# 1_Controller.net
KiCad netlist of a schematic drawn in Altium Designer
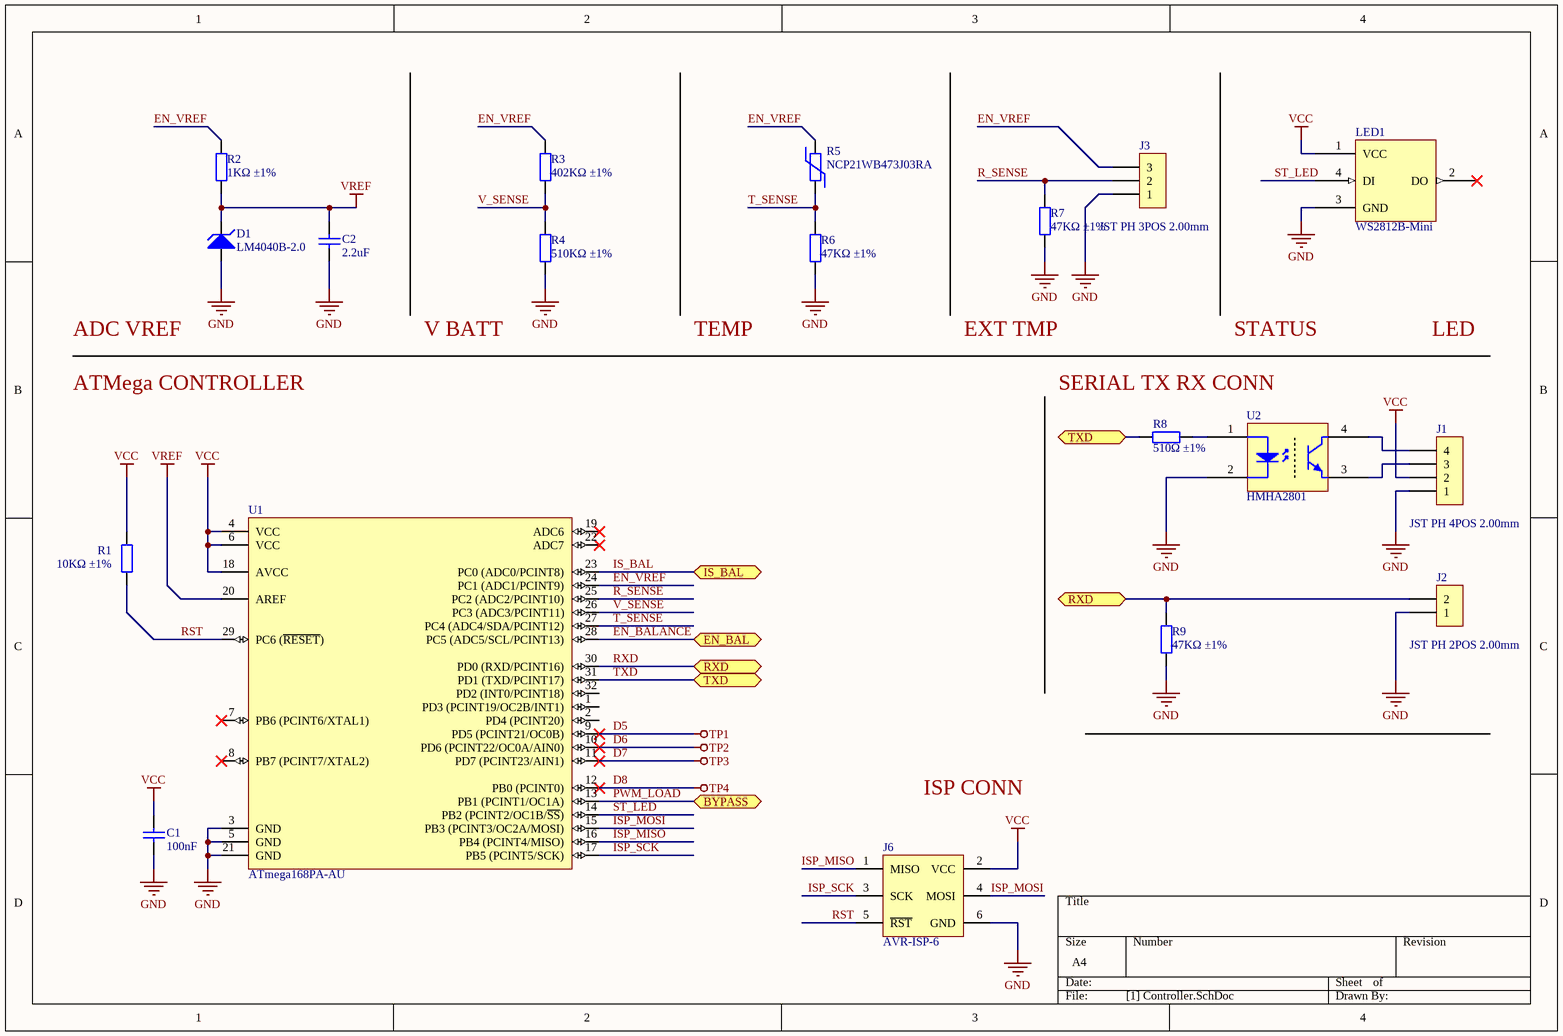
[diagram p0: [1] Controller.SchDoc]

(export (version "E")
  (design (tool "Eeschema 10.0.6"))
  (components
    (comp (ref "C1")
      (value "100nF")
      (footprint "0805_C")
      (description "Chip capacitors")
      (fields (field (name "MANUFACTURER") "YAGEO") (field (name "PARTNUMBER") "CC0805KRX7R9BB104"))
      (libsource (lib "Miscellaneous Devices LC") (part "0805 100nF(104) 10% 50V"))
    )
    (comp (ref "C2")
      (value "2.2uF")
      (footprint "0805_C")
      (description "Chip capacitors")
      (fields
        (field (name "MANUFACTURER") "Guangdong Fenghua Advanced Tech")
        (field (name "PARTNUMBER") "0805F225M500NT")
      )
      (libsource (lib "Miscellaneous Devices LC") (part "0805 2.2uF (225) 20% 50V"))
    )
    (comp (ref "D1")
      (value "LM4040B-2.0")
      (footprint "SOT-23(SOT-23-3)")
      (description "Precision Shunt Voltage Reference")
      (libsource (lib "BMS_SchLib") (part "LM4040B-2.0"))
    )
    (comp (ref "J1")
      (value "JST PH 4POS 2.00mm")
      (footprint "JST_PH_S4B")
      (description "JST-PH Conn")
      (fields
        (field (name "MANUFACTURER") "JST Sales America")
        (field (name "PARTNUMBER") "S4B-PH-K-S(LF)(SN)")
      )
      (libsource (lib "BMS_SchLib") (part "JST_PH_4POS"))
    )
    (comp (ref "J2")
      (value "JST PH 2POS 2.00mm")
      (footprint "JST_PH_S2B")
      (description "JST-PH Conn")
      (fields
        (field (name "MANUFACTURER") "JST Sales America")
        (field (name "PARTNUMBER") "S2B-PH-K-S(LF)(SN)")
      )
      (libsource (lib "BMS_SchLib") (part "JST_PH_2POS"))
    )
    (comp (ref "J3")
      (value "JST PH 3POS 2.00mm")
      (footprint "JST_PH_S3B")
      (description "JST-PH Conn")
      (fields
        (field (name "MANUFACTURER") "JST Sales America")
        (field (name "PARTNUMBER") "S3B-PH-K-S(LF)(SN)")
      )
      (libsource (lib "BMS_SchLib") (part "JST_PH_3POS"))
    )
    (comp (ref "J6")
      (value "AVR-ISP-6")
      (footprint "PINHEADER_6POS_2ROW_2.54")
      (fields (field (name "MANUFACTURER") "Boom Precision Elec") (field (name "PARTNUMBER") "C65114"))
      (libsource (lib "BMS_SchLib") (part "AVR_ISP"))
    )
    (comp (ref "LED1")
      (value "WS2812B-Mini")
      (footprint "LED3535_4P")
      (description "RGB Addressable LED")
      (fields (field (name "MANUFACTURER") "Worldsemi"))
      (libsource (lib "BMS_SchLib") (part "WS2812B-Mini"))
    )
    (comp (ref "R1")
      (value "10KΩ ±1%")
      (footprint "0805_R")
      (description "Chip resistor")
      (fields (field (name "MANUFACTURER") "Uniroyal Elec") (field (name "PARTNUMBER") "0805W8F1002T5E"))
      (libsource (lib "RES") (part "0805 10K (1002) 1%"))
    )
    (comp (ref "R2")
      (value "1KΩ ±1%")
      (footprint "0805_R")
      (description "Chip resistor")
      (fields (field (name "MANUFACTURER") "Uniroyal Elec") (field (name "PARTNUMBER") "0805W8F1001T5E"))
      (libsource (lib "RES") (part "0805 1K (1001) 1%"))
    )
    (comp (ref "R3")
      (value "402KΩ ±1%")
      (footprint "0805_R")
      (description "Chip resistor")
      (fields (field (name "MANUFACTURER") "Uniroyal Elec") (field (name "PARTNUMBER") "0805W8F4023T5E"))
      (libsource (lib "BMS_SchLib") (part "0805 402K (4023) 1%"))
    )
    (comp (ref "R4")
      (value "510KΩ ±1%")
      (footprint "0805_R")
      (description "Chip resistor")
      (fields (field (name "MANUFACTURER") "Uniroyal Elec") (field (name "PARTNUMBER") "0805W8F4023T5E"))
      (libsource (lib "BMS_SchLib") (part "0805 510K (5103) 1%"))
    )
    (comp (ref "R5")
      (value "NCP21WB473J03RA")
      (footprint "0805_R")
      (description "NTC Resistor 47K 5%")
      (fields (field (name "MANUFACTURER") "Murata Electronics") (field (name "TOLERANCE") "5%"))
      (libsource (lib "BMS_SchLib") (part "0805 NTC 47K 5%"))
    )
    (comp (ref "R6")
      (value "47KΩ ±1%")
      (footprint "0805_R")
      (description "Chip resistor")
      (fields (field (name "MANUFACTURER") "Uniroyal Elec") (field (name "PARTNUMBER") "0805W8F4702T5E"))
      (libsource (lib "RES") (part "0805 47K (4702) 1%"))
    )
    (comp (ref "R7")
      (value "47KΩ ±1%")
      (footprint "0805_R")
      (description "Chip resistor")
      (fields (field (name "MANUFACTURER") "Uniroyal Elec") (field (name "PARTNUMBER") "0805W8F4702T5E"))
      (libsource (lib "RES") (part "0805 47K (4702) 1%"))
    )
    (comp (ref "R8")
      (value "510Ω ±1%")
      (footprint "0805_R")
      (description "Chip resistor")
      (fields (field (name "MANUFACTURER") "Uniroyal Elec") (field (name "PARTNUMBER") "0805W8F5100T5E"))
      (libsource (lib "RES") (part "0805 510R (5100) 1%"))
    )
    (comp (ref "R9")
      (value "47KΩ ±1%")
      (footprint "0805_R")
      (description "Chip resistor")
      (fields (field (name "MANUFACTURER") "Uniroyal Elec") (field (name "PARTNUMBER") "0805W8F4702T5E"))
      (libsource (lib "RES") (part "0805 47K (4702) 1%"))
    )
    (comp (ref "U1")
      (value "ATmega168PA-AU")
      (footprint "TQFP-32_7x7x08P")
      (description "ATmega AVR")
      (fields (field (name "MANUFACTURER") "Microchip Tech") (field (name "PARTNUMBER") "ATMEGA168PA-AU"))
      (libsource (lib "BMS_SchLib") (part "ATMEGA168"))
    )
    (comp (ref "U2")
      (value "HMHA2801")
      (footprint "HMHA2801")
      (description "Optocoupler")
      (fields (field (name "MANUFACTURER") "ON Semicon") (field (name "PARTNUMBER") "HMHA2801AR2"))
      (libsource (lib "BMS_SchLib") (part "HMHA2801"))
    )
  )
  (nets
    (net (code "1") (name "/EN_BALANCE") (class "Default")
      (node (ref "U1") (pin "28") (pinfunction "PC5_(ADC5/SCL/PCINT13)_28") (pintype "bidirectional"))
    )
    (net (code "2") (name "/EN_VREF") (class "Default")
      (node (ref "J3") (pin "3") (pinfunction "3_3") (pintype "passive"))
      (node (ref "R2") (pin "2") (pinfunction "2_2") (pintype "passive"))
      (node (ref "R3") (pin "2") (pinfunction "2_2") (pintype "passive"))
      (node (ref "R5") (pin "2") (pinfunction "2_2") (pintype "passive"))
      (node (ref "U1") (pin "24") (pinfunction "PC1_(ADC1/PCINT9)_24") (pintype "bidirectional"))
    )
    (net (code "3") (name "/ISP_MISO") (class "Default")
      (node (ref "J6") (pin "1") (pinfunction "MISO_1") (pintype "passive"))
      (node (ref "U1") (pin "16") (pinfunction "PB4_(PCINT4/MISO)_16") (pintype "bidirectional"))
    )
    (net (code "4") (name "/ISP_MOSI") (class "Default")
      (node (ref "J6") (pin "4") (pinfunction "MOSI_4") (pintype "passive"))
      (node (ref "U1") (pin "15") (pinfunction "PB3_(PCINT3/OC2A/MOSI)_15") (pintype "bidirectional"))
    )
    (net (code "5") (name "/ISP_SCK") (class "Default")
      (node (ref "J6") (pin "3") (pinfunction "SCK_3") (pintype "passive"))
      (node (ref "U1") (pin "17") (pinfunction "PB5_(PCINT5/SCK)_17") (pintype "bidirectional"))
    )
    (net (code "6") (name "/IS_BAL") (class "Default")
      (node (ref "U1") (pin "23") (pinfunction "PC0_(ADC0/PCINT8)_23") (pintype "bidirectional"))
    )
    (net (code "7") (name "/PWM_LOAD") (class "Default")
      (node (ref "U1") (pin "13") (pinfunction "PB1_(PCINT1/OC1A)_13") (pintype "bidirectional"))
    )
    (net (code "8") (name "/RST") (class "Default")
      (node (ref "J6") (pin "5") (pinfunction "~{RST}_5") (pintype "passive"))
      (node (ref "R1") (pin "2") (pinfunction "2_2") (pintype "passive"))
      (node (ref "U1") (pin "29") (pinfunction "PC6_(~{RESET})_29") (pintype "bidirectional"))
    )
    (net (code "9") (name "/RXD") (class "Default")
      (node (ref "J2") (pin "2") (pinfunction "2_2") (pintype "passive"))
      (node (ref "R9") (pin "2") (pinfunction "2_2") (pintype "passive"))
      (node (ref "U1") (pin "30") (pinfunction "PD0_(RXD/PCINT16)_30") (pintype "bidirectional"))
    )
    (net (code "10") (name "/R_SENSE") (class "Default")
      (node (ref "J3") (pin "2") (pinfunction "2_2") (pintype "passive"))
      (node (ref "R7") (pin "2") (pinfunction "2_2") (pintype "passive"))
      (node (ref "U1") (pin "25") (pinfunction "PC2_(ADC2/PCINT10)_25") (pintype "bidirectional"))
    )
    (net (code "11") (name "/ST_LED") (class "Default")
      (node (ref "LED1") (pin "4") (pinfunction "DI_4") (pintype "input"))
      (node (ref "U1") (pin "14") (pinfunction "PB2_(PCINT2/OC1B/~{SS})_14") (pintype "bidirectional"))
    )
    (net (code "12") (name "/TXD") (class "Default")
      (node (ref "R8") (pin "1") (pinfunction "1_1") (pintype "passive"))
      (node (ref "U1") (pin "31") (pinfunction "PD1_(TXD/PCINT17)_31") (pintype "bidirectional"))
    )
    (net (code "13") (name "/T_SENSE") (class "Default")
      (node (ref "R5") (pin "1") (pinfunction "1_1") (pintype "passive"))
      (node (ref "R6") (pin "2") (pinfunction "2_2") (pintype "passive"))
      (node (ref "U1") (pin "27") (pinfunction "PC4_(ADC4/SDA/PCINT12)_27") (pintype "bidirectional"))
    )
    (net (code "14") (name "/V_SENSE") (class "Default")
      (node (ref "R3") (pin "1") (pinfunction "1_1") (pintype "passive"))
      (node (ref "R4") (pin "2") (pinfunction "2_2") (pintype "passive"))
      (node (ref "U1") (pin "26") (pinfunction "PC3_(ADC3/PCINT11)_26") (pintype "bidirectional"))
    )
    (net (code "15") (name "GND") (class "Default")
      (node (ref "C1") (pin "1") (pinfunction "1_1") (pintype "passive"))
      (node (ref "C2") (pin "1") (pinfunction "1_1") (pintype "passive"))
      (node (ref "D1") (pin "2") (pinfunction "A_2") (pintype "passive"))
      (node (ref "J1") (pin "1") (pinfunction "1_1") (pintype "passive"))
      (node (ref "J2") (pin "1") (pinfunction "1_1") (pintype "passive"))
      (node (ref "J3") (pin "1") (pinfunction "1_1") (pintype "passive"))
      (node (ref "J6") (pin "6") (pinfunction "GND_6") (pintype "power_in"))
      (node (ref "LED1") (pin "3") (pinfunction "GND_3") (pintype "power_in"))
      (node (ref "R4") (pin "1") (pinfunction "1_1") (pintype "passive"))
      (node (ref "R6") (pin "1") (pinfunction "1_1") (pintype "passive"))
      (node (ref "R7") (pin "1") (pinfunction "1_1") (pintype "passive"))
      (node (ref "R9") (pin "1") (pinfunction "1_1") (pintype "passive"))
      (node (ref "U1") (pin "21") (pinfunction "GND_21") (pintype "power_in"))
      (node (ref "U1") (pin "3") (pinfunction "GND_3") (pintype "power_in"))
      (node (ref "U1") (pin "5") (pinfunction "GND_5") (pintype "power_in"))
      (node (ref "U2") (pin "2") (pinfunction "A_2") (pintype "passive"))
    )
    (net (code "16") (name "Net-(J1-Pad3)") (class "Default")
      (node (ref "J1") (pin "3") (pinfunction "3_3") (pintype "passive"))
      (node (ref "U2") (pin "3") (pintype "passive"))
    )
    (net (code "17") (name "Net-(J1-Pad4)") (class "Default")
      (node (ref "J1") (pin "4") (pinfunction "4_4") (pintype "passive"))
      (node (ref "U2") (pin "4") (pintype "passive"))
    )
    (net (code "18") (name "Net-(R8-Pad2)") (class "Default")
      (node (ref "R8") (pin "2") (pinfunction "2_2") (pintype "passive"))
      (node (ref "U2") (pin "1") (pintype "passive"))
    )
    (net (code "19") (name "TP1") (class "Default")
      (node (ref "U1") (pin "9") (pinfunction "PD5_(PCINT21/OC0B)_9") (pintype "bidirectional"))
    )
    (net (code "20") (name "TP2") (class "Default")
      (node (ref "U1") (pin "10") (pinfunction "PD6_(PCINT22/OC0A/AIN0)_10") (pintype "bidirectional"))
    )
    (net (code "21") (name "TP3") (class "Default")
      (node (ref "U1") (pin "11") (pinfunction "PD7_(PCINT23/AIN1)_11") (pintype "bidirectional"))
    )
    (net (code "22") (name "TP4") (class "Default")
      (node (ref "U1") (pin "12") (pinfunction "PB0_(PCINT0)_12") (pintype "bidirectional"))
    )
    (net (code "23") (name "VCC") (class "Default")
      (node (ref "C1") (pin "2") (pinfunction "2_2") (pintype "passive"))
      (node (ref "J1") (pin "2") (pinfunction "2_2") (pintype "passive"))
      (node (ref "J6") (pin "2") (pinfunction "VCC_2") (pintype "power_in"))
      (node (ref "LED1") (pin "1") (pinfunction "VCC_1") (pintype "power_in"))
      (node (ref "R1") (pin "1") (pinfunction "1_1") (pintype "passive"))
      (node (ref "U1") (pin "18") (pinfunction "AVCC_18") (pintype "passive"))
      (node (ref "U1") (pin "4") (pinfunction "VCC_4") (pintype "passive"))
      (node (ref "U1") (pin "6") (pinfunction "VCC_6") (pintype "passive"))
    )
    (net (code "24") (name "VREF") (class "Default")
      (node (ref "C2") (pin "2") (pinfunction "2_2") (pintype "passive"))
      (node (ref "D1") (pin "1") (pinfunction "K_1") (pintype "passive"))
      (node (ref "R2") (pin "1") (pinfunction "1_1") (pintype "passive"))
      (node (ref "U1") (pin "20") (pinfunction "AREF_20") (pintype "passive"))
    )
    (net (code "25") (name "unconnected-(LED1-DO-Pad2)") (class "Default")
      (node (ref "LED1") (pin "2") (pinfunction "DO_2") (pintype "output+no_connect"))
    )
    (net (code "26") (name "unconnected-(U1-ADC6-Pad19)") (class "Default")
      (node (ref "U1") (pin "19") (pinfunction "ADC6_19") (pintype "bidirectional+no_connect"))
    )
    (net (code "27") (name "unconnected-(U1-ADC7-Pad22)") (class "Default")
      (node (ref "U1") (pin "22") (pinfunction "ADC7_22") (pintype "bidirectional+no_connect"))
    )
    (net (code "28") (name "unconnected-(U1-PB6_(PCINT6{slash}XTAL1)-Pad7)") (class "Default")
      (node (ref "U1") (pin "7") (pinfunction "PB6_(PCINT6/XTAL1)_7") (pintype "bidirectional+no_connect"))
    )
    (net (code "29") (name "unconnected-(U1-PB7_(PCINT7{slash}XTAL2)-Pad8)") (class "Default")
      (node (ref "U1") (pin "8") (pinfunction "PB7_(PCINT7/XTAL2)_8") (pintype "bidirectional+no_connect"))
    )
    (net (code "30") (name "unconnected-(U1-PD2_(INT0{slash}PCINT18)-Pad32)") (class "Default")
      (node (ref "U1") (pin "32") (pinfunction "PD2_(INT0/PCINT18)_32") (pintype "bidirectional"))
    )
    (net (code "31") (name "unconnected-(U1-PD3_(PCINT19{slash}OC2B{slash}INT1)-Pad1)") (class "Default")
      (node (ref "U1") (pin "1") (pinfunction "PD3_(PCINT19/OC2B/INT1)_1") (pintype "bidirectional"))
    )
    (net (code "32") (name "unconnected-(U1-PD4_(PCINT20)-Pad2)") (class "Default")
      (node (ref "U1") (pin "2") (pinfunction "PD4_(PCINT20)_2") (pintype "bidirectional"))
    )
  )
)
